# Alimentacion_doble.net
KiCad netlist of a schematic drawn in EAGLE
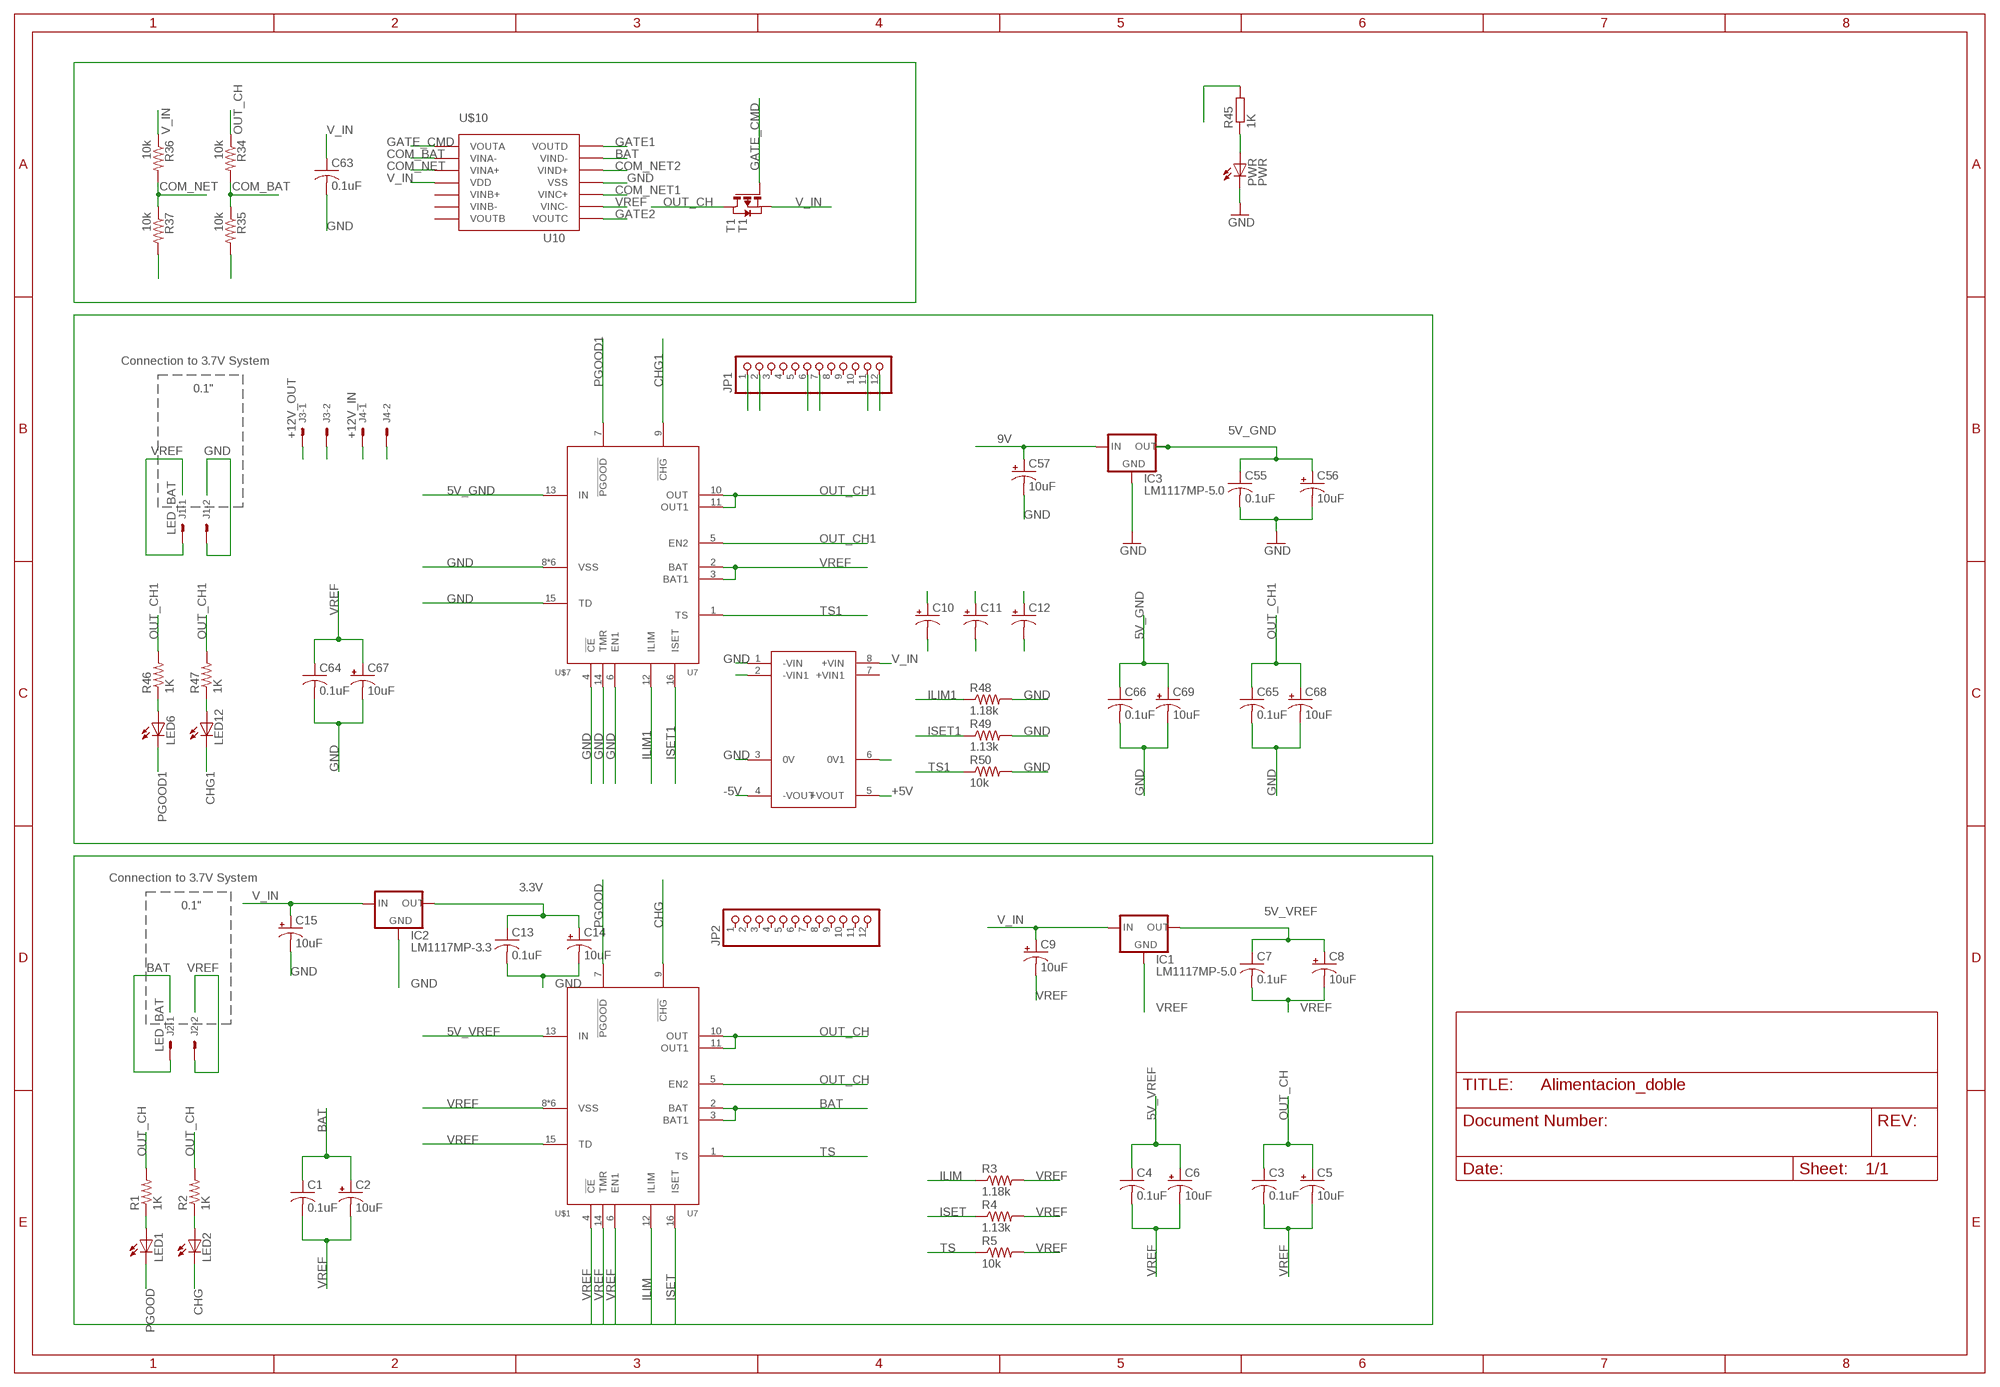
[diagram p0: schematic, sheet 1]

(export (version "E")
  (design (tool "Eeschema 10.0.6"))
  (components
    (comp (ref "C1")
      (value "0.1uF")
      (footprint "eagle-import:C0805K")
      (libsource (lib "eagle-import") (part "C-USC0805K"))
    )
    (comp (ref "C2")
      (value "10uF")
      (footprint "eagle-import:B_3528-21W")
      (libsource (lib "eagle-import") (part "CPOL-USB/3528-21W"))
    )
    (comp (ref "C3")
      (value "0.1uF")
      (footprint "eagle-import:C0805K")
      (libsource (lib "eagle-import") (part "C-USC0805K"))
    )
    (comp (ref "C4")
      (value "0.1uF")
      (footprint "eagle-import:C0805K")
      (libsource (lib "eagle-import") (part "C-USC0805K"))
    )
    (comp (ref "C5")
      (value "10uF")
      (footprint "eagle-import:B_3528-21W")
      (libsource (lib "eagle-import") (part "CPOL-USB/3528-21W"))
    )
    (comp (ref "C6")
      (value "10uF")
      (footprint "eagle-import:B_3528-21W")
      (libsource (lib "eagle-import") (part "CPOL-USB/3528-21W"))
    )
    (comp (ref "C7")
      (value "0.1uF")
      (footprint "eagle-import:C0805K")
      (libsource (lib "eagle-import") (part "C-USC0805K"))
    )
    (comp (ref "C8")
      (value "10uF")
      (footprint "eagle-import:B_3528-21W")
      (libsource (lib "eagle-import") (part "CPOL-USB/3528-21W"))
    )
    (comp (ref "C9")
      (value "10uF")
      (footprint "eagle-import:B_3528-21W")
      (libsource (lib "eagle-import") (part "CPOL-USB/3528-21W"))
    )
    (comp (ref "C10")
      (value "CPOL-USB/3528-21W")
      (footprint "eagle-import:B_3528-21W")
      (libsource (lib "eagle-import") (part "CPOL-USB/3528-21W"))
    )
    (comp (ref "C11")
      (value "CPOL-USB/3528-21W")
      (footprint "eagle-import:B_3528-21W")
      (libsource (lib "eagle-import") (part "CPOL-USB/3528-21W"))
    )
    (comp (ref "C12")
      (value "CPOL-USB/3528-21W")
      (footprint "eagle-import:B_3528-21W")
      (libsource (lib "eagle-import") (part "CPOL-USB/3528-21W"))
    )
    (comp (ref "C13")
      (value "0.1uF")
      (footprint "eagle-import:C0805K")
      (libsource (lib "eagle-import") (part "C-USC0805K"))
    )
    (comp (ref "C14")
      (value "10uF")
      (footprint "eagle-import:B_3528-21W")
      (libsource (lib "eagle-import") (part "CPOL-USB/3528-21W"))
    )
    (comp (ref "C15")
      (value "10uF")
      (footprint "eagle-import:B_3528-21W")
      (libsource (lib "eagle-import") (part "CPOL-USB/3528-21W"))
    )
    (comp (ref "C55")
      (value "0.1uF")
      (footprint "eagle-import:C0805K")
      (libsource (lib "eagle-import") (part "C-USC0805K"))
    )
    (comp (ref "C56")
      (value "10uF")
      (footprint "eagle-import:B_3528-21W")
      (libsource (lib "eagle-import") (part "CPOL-USB/3528-21W"))
    )
    (comp (ref "C57")
      (value "10uF")
      (footprint "eagle-import:B_3528-21W")
      (libsource (lib "eagle-import") (part "CPOL-USB/3528-21W"))
    )
    (comp (ref "C63")
      (value "0.1uF")
      (footprint "eagle-import:C0805K")
      (libsource (lib "eagle-import") (part "C-USC0805K"))
    )
    (comp (ref "C64")
      (value "0.1uF")
      (footprint "eagle-import:C0805K")
      (libsource (lib "eagle-import") (part "C-USC0805K"))
    )
    (comp (ref "C65")
      (value "0.1uF")
      (footprint "eagle-import:C0805K")
      (libsource (lib "eagle-import") (part "C-USC0805K"))
    )
    (comp (ref "C66")
      (value "0.1uF")
      (footprint "eagle-import:C0805K")
      (libsource (lib "eagle-import") (part "C-USC0805K"))
    )
    (comp (ref "C67")
      (value "10uF")
      (footprint "eagle-import:B_3528-21W")
      (libsource (lib "eagle-import") (part "CPOL-USB/3528-21W"))
    )
    (comp (ref "C68")
      (value "10uF")
      (footprint "eagle-import:B_3528-21W")
      (libsource (lib "eagle-import") (part "CPOL-USB/3528-21W"))
    )
    (comp (ref "C69")
      (value "10uF")
      (footprint "eagle-import:B_3528-21W")
      (libsource (lib "eagle-import") (part "CPOL-USB/3528-21W"))
    )
    (comp (ref "IC1")
      (value "LM1117MP-5.0")
      (footprint "eagle-import:SOT223")
      (fields (field (name "MF") "Texas Instruments"))
      (libsource (lib "eagle-import") (part "LM1117?-MP5.0"))
    )
    (comp (ref "IC2")
      (value "LM1117MP-3.3")
      (footprint "eagle-import:SOT223")
      (fields (field (name "MF") "Texas Instruments") (field (name "MPN") "LM1117MP-5.0"))
      (libsource (lib "eagle-import") (part "LM1117?-MP5.0"))
    )
    (comp (ref "IC3")
      (value "LM1117MP-5.0")
      (footprint "eagle-import:SOT223")
      (fields (field (name "MF") "Texas Instruments"))
      (libsource (lib "eagle-import") (part "LM1117?-MP5.0"))
    )
    (comp (ref "J1")
      (value "LED_BAT")
      (footprint "eagle-import:6410-02")
      (libsource (lib "eagle-import") (part "22-?-0227-2021"))
    )
    (comp (ref "J2")
      (value "LED_BAT")
      (footprint "eagle-import:6410-02")
      (libsource (lib "eagle-import") (part "22-?-0227-2021"))
    )
    (comp (ref "J3")
      (value "+12V_OUT")
      (footprint "eagle-import:6410-02")
      (fields (field (name "OC_FARNELL") "unknown") (field (name "OC_NEWARK") "unknown"))
      (libsource (lib "eagle-import") (part "22-?-0227-2021"))
    )
    (comp (ref "J4")
      (value "+12V_IN")
      (footprint "eagle-import:6410-02")
      (fields (field (name "OC_FARNELL") "unknown") (field (name "OC_NEWARK") "unknown"))
      (libsource (lib "eagle-import") (part "22-?-0227-2021"))
    )
    (comp (ref "JP1")
      (value "PINHD-1X12")
      (footprint "eagle-import:1X12")
      (libsource (lib "eagle-import") (part "PINHD-1X12"))
    )
    (comp (ref "JP2")
      (value "PINHD-1X12")
      (footprint "eagle-import:1X12")
      (libsource (lib "eagle-import") (part "PINHD-1X12"))
    )
    (comp (ref "LED1")
      (value "LED3MM")
      (footprint "eagle-import:LED3MM")
      (libsource (lib "eagle-import") (part "LED3MM"))
    )
    (comp (ref "LED2")
      (value "LED3MM")
      (footprint "eagle-import:LED3MM")
      (libsource (lib "eagle-import") (part "LED3MM"))
    )
    (comp (ref "LED6")
      (value "LED3MM")
      (footprint "eagle-import:LED3MM")
      (libsource (lib "eagle-import") (part "LED3MM"))
    )
    (comp (ref "LED12")
      (value "LED3MM")
      (footprint "eagle-import:LED3MM")
      (libsource (lib "eagle-import") (part "LED3MM"))
    )
    (comp (ref "PWR")
      (value "PWR")
      (footprint "eagle-import:LED3MM")
      (libsource (lib "eagle-import") (part "LED3MM"))
    )
    (comp (ref "R1")
      (value "1K")
      (footprint "eagle-import:M0805")
      (libsource (lib "eagle-import") (part "R-US_M0805"))
    )
    (comp (ref "R2")
      (value "1K")
      (footprint "eagle-import:M0805")
      (libsource (lib "eagle-import") (part "R-US_M0805"))
    )
    (comp (ref "R3")
      (value "1.18k")
      (footprint "eagle-import:M0805")
      (libsource (lib "eagle-import") (part "R-US_M0805"))
    )
    (comp (ref "R4")
      (value "1.13k")
      (footprint "eagle-import:M0805")
      (libsource (lib "eagle-import") (part "R-US_M0805"))
    )
    (comp (ref "R5")
      (value "10k")
      (footprint "eagle-import:M0805")
      (libsource (lib "eagle-import") (part "R-US_M0805"))
    )
    (comp (ref "R34")
      (value "10k")
      (footprint "eagle-import:M0805")
      (libsource (lib "eagle-import") (part "R-US_M0805"))
    )
    (comp (ref "R35")
      (value "10k")
      (footprint "eagle-import:M0805")
      (libsource (lib "eagle-import") (part "R-US_M0805"))
    )
    (comp (ref "R36")
      (value "10k")
      (footprint "eagle-import:M0805")
      (libsource (lib "eagle-import") (part "R-US_M0805"))
    )
    (comp (ref "R37")
      (value "10k")
      (footprint "eagle-import:M0805")
      (libsource (lib "eagle-import") (part "R-US_M0805"))
    )
    (comp (ref "R45")
      (value "1K")
      (footprint "eagle-import:R0805")
      (libsource (lib "eagle-import") (part "R-EU_R0805"))
    )
    (comp (ref "R46")
      (value "1K")
      (footprint "eagle-import:M0805")
      (libsource (lib "eagle-import") (part "R-US_M0805"))
    )
    (comp (ref "R47")
      (value "1K")
      (footprint "eagle-import:M0805")
      (libsource (lib "eagle-import") (part "R-US_M0805"))
    )
    (comp (ref "R48")
      (value "1.18k")
      (footprint "eagle-import:M0805")
      (libsource (lib "eagle-import") (part "R-US_M0805"))
    )
    (comp (ref "R49")
      (value "1.13k")
      (footprint "eagle-import:M0805")
      (libsource (lib "eagle-import") (part "R-US_M0805"))
    )
    (comp (ref "R50")
      (value "10k")
      (footprint "eagle-import:M0805")
      (libsource (lib "eagle-import") (part "R-US_M0805"))
    )
    (comp (ref "T1")
      (value "T1")
      (footprint "eagle-import:SOT-23")
      (libsource (lib "eagle-import") (part "PMOSSOT23"))
    )
    (comp (ref "U$1")
      (value "U7")
      (footprint "eagle-import:BQ24232")
      (libsource (lib "eagle-import") (part "BQ24072VQFN-16"))
    )
    (comp (ref "U$2")
      (value "NDTD_CONVERTER")
      (footprint "eagle-import:NDTD_CONVERTER")
      (libsource (lib "eagle-import") (part "NDTD_CONVERTER"))
    )
    (comp (ref "U$7")
      (value "U7")
      (footprint "eagle-import:BQ24232")
      (libsource (lib "eagle-import") (part "BQ24072VQFN-16"))
    )
    (comp (ref "U$10")
      (value "U10")
      (footprint "eagle-import:MCP6294")
      (libsource (lib "eagle-import") (part "MCP6294TSSOP-14"))
    )
  )
  (nets
    (net (code "1") (name "/+5V") (class "Default")
      (node (ref "C12") (pin "+") (pinfunction "+_+") (pintype "passive"))
      (node (ref "JP1") (pin "1") (pinfunction "1_1") (pintype "passive"))
      (node (ref "U$2") (pin "5") (pinfunction "+VOUT_5") (pintype "bidirectional"))
    )
    (net (code "2") (name "/-5V") (class "Default")
      (node (ref "C11") (pin "+") (pinfunction "+_+") (pintype "passive"))
      (node (ref "JP1") (pin "12") (pinfunction "12_12") (pintype "passive"))
      (node (ref "U$2") (pin "4") (pinfunction "-VOUT_4") (pintype "bidirectional"))
    )
    (net (code "3") (name "/3.3V") (class "Default")
      (node (ref "C13") (pin "1") (pinfunction "1_1") (pintype "passive"))
      (node (ref "C14") (pin "+") (pinfunction "+_+") (pintype "passive"))
      (node (ref "IC2") (pin "2") (pinfunction "OUT_2") (pintype "passive"))
      (node (ref "IC2") (pin "4") (pinfunction "OUT_4") (pintype "passive"))
      (node (ref "JP1") (pin "6") (pinfunction "6_6") (pintype "passive"))
    )
    (net (code "4") (name "/5V_GND") (class "Default")
      (node (ref "C55") (pin "1") (pinfunction "1_1") (pintype "passive"))
      (node (ref "C56") (pin "+") (pinfunction "+_+") (pintype "passive"))
      (node (ref "C66") (pin "1") (pinfunction "1_1") (pintype "passive"))
      (node (ref "C69") (pin "+") (pinfunction "+_+") (pintype "passive"))
      (node (ref "IC3") (pin "2") (pinfunction "OUT_2") (pintype "passive"))
      (node (ref "IC3") (pin "4") (pinfunction "OUT_4") (pintype "passive"))
      (node (ref "U$7") (pin "13") (pinfunction "IN_13") (pintype "bidirectional"))
    )
    (net (code "5") (name "/5V_VREF") (class "Default")
      (node (ref "C4") (pin "1") (pinfunction "1_1") (pintype "passive"))
      (node (ref "C6") (pin "+") (pinfunction "+_+") (pintype "passive"))
      (node (ref "C7") (pin "1") (pinfunction "1_1") (pintype "passive"))
      (node (ref "C8") (pin "+") (pinfunction "+_+") (pintype "passive"))
      (node (ref "IC1") (pin "2") (pinfunction "OUT_2") (pintype "passive"))
      (node (ref "IC1") (pin "4") (pinfunction "OUT_4") (pintype "passive"))
      (node (ref "U$1") (pin "13") (pinfunction "IN_13") (pintype "bidirectional"))
    )
    (net (code "6") (name "/9V") (class "Default")
      (node (ref "C57") (pin "+") (pinfunction "+_+") (pintype "passive"))
      (node (ref "IC3") (pin "3") (pinfunction "IN_3") (pintype "input"))
    )
    (net (code "7") (name "/BAT") (class "Default")
      (node (ref "C1") (pin "1") (pinfunction "1_1") (pintype "passive"))
      (node (ref "C2") (pin "+") (pinfunction "+_+") (pintype "passive"))
      (node (ref "J2") (pin "1") (pinfunction "S_1") (pintype "passive"))
      (node (ref "U$1") (pin "2") (pinfunction "BAT_2") (pintype "bidirectional"))
      (node (ref "U$1") (pin "3") (pinfunction "BAT1_3") (pintype "bidirectional"))
      (node (ref "U$10") (pin "VIND-") (pinfunction "VIND-_VIND-") (pintype "bidirectional"))
    )
    (net (code "8") (name "/CHG") (class "Default")
      (node (ref "LED2") (pin "K") (pinfunction "C_K") (pintype "passive"))
      (node (ref "U$1") (pin "9") (pinfunction "~{CHG}_9") (pintype "bidirectional"))
    )
    (net (code "9") (name "/CHG1") (class "Default")
      (node (ref "LED12") (pin "K") (pinfunction "C_K") (pintype "passive"))
      (node (ref "U$7") (pin "9") (pinfunction "~{CHG}_9") (pintype "bidirectional"))
    )
    (net (code "10") (name "/COM_BAT") (class "Default")
      (node (ref "R34") (pin "2") (pinfunction "2_2") (pintype "passive"))
      (node (ref "R35") (pin "1") (pinfunction "1_1") (pintype "passive"))
      (node (ref "U$10") (pin "VINA-") (pinfunction "VINA-_VINA-") (pintype "bidirectional"))
    )
    (net (code "11") (name "/COM_NET") (class "Default")
      (node (ref "R36") (pin "2") (pinfunction "2_2") (pintype "passive"))
      (node (ref "R37") (pin "1") (pinfunction "1_1") (pintype "passive"))
      (node (ref "U$10") (pin "VINA+") (pinfunction "VINA+_VINA+") (pintype "bidirectional"))
    )
    (net (code "12") (name "/COM_NET1") (class "Default")
      (node (ref "U$10") (pin "VINC+") (pinfunction "VINC+_VINC+") (pintype "bidirectional"))
    )
    (net (code "13") (name "/COM_NET2") (class "Default")
      (node (ref "U$10") (pin "VIND+") (pinfunction "VIND+_VIND+") (pintype "bidirectional"))
    )
    (net (code "14") (name "/GATE1") (class "Default")
      (node (ref "U$10") (pin "VOUTD") (pinfunction "VOUTD_VOUTD") (pintype "bidirectional"))
    )
    (net (code "15") (name "/GATE2") (class "Default")
      (node (ref "U$10") (pin "VOUTC") (pinfunction "VOUTC_VOUTC") (pintype "bidirectional"))
    )
    (net (code "16") (name "/GATE_CMD") (class "Default")
      (node (ref "T1") (pin "3") (pinfunction "G_3") (pintype "passive"))
      (node (ref "U$10") (pin "VOUTA") (pinfunction "VOUTA_VOUTA") (pintype "bidirectional"))
    )
    (net (code "17") (name "/ILIM") (class "Default")
      (node (ref "R3") (pin "1") (pinfunction "1_1") (pintype "passive"))
      (node (ref "U$1") (pin "12") (pinfunction "ILIM_12") (pintype "bidirectional"))
    )
    (net (code "18") (name "/ILIM1") (class "Default")
      (node (ref "R48") (pin "1") (pinfunction "1_1") (pintype "passive"))
      (node (ref "U$7") (pin "12") (pinfunction "ILIM_12") (pintype "bidirectional"))
    )
    (net (code "19") (name "/ISET") (class "Default")
      (node (ref "R4") (pin "1") (pinfunction "1_1") (pintype "passive"))
      (node (ref "U$1") (pin "16") (pinfunction "ISET_16") (pintype "bidirectional"))
    )
    (net (code "20") (name "/ISET1") (class "Default")
      (node (ref "R49") (pin "1") (pinfunction "1_1") (pintype "passive"))
      (node (ref "U$7") (pin "16") (pinfunction "ISET_16") (pintype "bidirectional"))
    )
    (net (code "21") (name "/OUT_CH") (class "Default")
      (node (ref "C3") (pin "1") (pinfunction "1_1") (pintype "passive"))
      (node (ref "C5") (pin "+") (pinfunction "+_+") (pintype "passive"))
      (node (ref "R1") (pin "2") (pinfunction "2_2") (pintype "passive"))
      (node (ref "R2") (pin "2") (pinfunction "2_2") (pintype "passive"))
      (node (ref "R34") (pin "1") (pinfunction "1_1") (pintype "passive"))
      (node (ref "T1") (pin "1") (pinfunction "D_1") (pintype "passive"))
      (node (ref "U$1") (pin "10") (pinfunction "OUT_10") (pintype "bidirectional"))
      (node (ref "U$1") (pin "11") (pinfunction "OUT1_11") (pintype "bidirectional"))
      (node (ref "U$1") (pin "5") (pinfunction "EN2_5") (pintype "bidirectional"))
    )
    (net (code "22") (name "/OUT_CH1") (class "Default")
      (node (ref "C65") (pin "1") (pinfunction "1_1") (pintype "passive"))
      (node (ref "C68") (pin "+") (pinfunction "+_+") (pintype "passive"))
      (node (ref "R46") (pin "2") (pinfunction "2_2") (pintype "passive"))
      (node (ref "R47") (pin "2") (pinfunction "2_2") (pintype "passive"))
      (node (ref "U$7") (pin "10") (pinfunction "OUT_10") (pintype "bidirectional"))
      (node (ref "U$7") (pin "11") (pinfunction "OUT1_11") (pintype "bidirectional"))
      (node (ref "U$7") (pin "5") (pinfunction "EN2_5") (pintype "bidirectional"))
    )
    (net (code "23") (name "/PGOOD") (class "Default")
      (node (ref "LED1") (pin "K") (pinfunction "C_K") (pintype "passive"))
      (node (ref "U$1") (pin "7") (pinfunction "~{PGOOD}_7") (pintype "bidirectional"))
    )
    (net (code "24") (name "/PGOOD1") (class "Default")
      (node (ref "LED6") (pin "K") (pinfunction "C_K") (pintype "passive"))
      (node (ref "U$7") (pin "7") (pinfunction "~{PGOOD}_7") (pintype "bidirectional"))
    )
    (net (code "25") (name "/TS") (class "Default")
      (node (ref "R5") (pin "1") (pinfunction "1_1") (pintype "passive"))
      (node (ref "U$1") (pin "1") (pinfunction "TS_1") (pintype "bidirectional"))
    )
    (net (code "26") (name "/TS1") (class "Default")
      (node (ref "R50") (pin "1") (pinfunction "1_1") (pintype "passive"))
      (node (ref "U$7") (pin "1") (pinfunction "TS_1") (pintype "bidirectional"))
    )
    (net (code "27") (name "/VREF") (class "Default")
      (node (ref "C1") (pin "2") (pinfunction "2_2") (pintype "passive"))
      (node (ref "C2") (pin "-") (pinfunction "-_-") (pintype "passive"))
      (node (ref "C3") (pin "2") (pinfunction "2_2") (pintype "passive"))
      (node (ref "C4") (pin "2") (pinfunction "2_2") (pintype "passive"))
      (node (ref "C5") (pin "-") (pinfunction "-_-") (pintype "passive"))
      (node (ref "C6") (pin "-") (pinfunction "-_-") (pintype "passive"))
      (node (ref "C64") (pin "1") (pinfunction "1_1") (pintype "passive"))
      (node (ref "C67") (pin "+") (pinfunction "+_+") (pintype "passive"))
      (node (ref "C7") (pin "2") (pinfunction "2_2") (pintype "passive"))
      (node (ref "C8") (pin "-") (pinfunction "-_-") (pintype "passive"))
      (node (ref "C9") (pin "-") (pinfunction "-_-") (pintype "passive"))
      (node (ref "IC1") (pin "1") (pinfunction "GND_1") (pintype "input"))
      (node (ref "J1") (pin "1") (pinfunction "S_1") (pintype "passive"))
      (node (ref "J2") (pin "2") (pinfunction "S_2") (pintype "passive"))
      (node (ref "R3") (pin "2") (pinfunction "2_2") (pintype "passive"))
      (node (ref "R4") (pin "2") (pinfunction "2_2") (pintype "passive"))
      (node (ref "R5") (pin "2") (pinfunction "2_2") (pintype "passive"))
      (node (ref "U$1") (pin "14") (pinfunction "TMR_14") (pintype "bidirectional"))
      (node (ref "U$1") (pin "15") (pinfunction "TD_15") (pintype "bidirectional"))
      (node (ref "U$1") (pin "4") (pinfunction "~{CE}_4") (pintype "bidirectional"))
      (node (ref "U$1") (pin "6") (pinfunction "EN1_6") (pintype "bidirectional"))
      (node (ref "U$1") (pin "8") (pinfunction "VSS_8") (pintype "bidirectional"))
      (node (ref "U$1") (pin "NA0") (pinfunction "VSS_NA0") (pintype "bidirectional"))
      (node (ref "U$1") (pin "NA1") (pinfunction "VSS_NA1") (pintype "bidirectional"))
      (node (ref "U$1") (pin "NA2") (pinfunction "VSS_NA2") (pintype "bidirectional"))
      (node (ref "U$1") (pin "NA3") (pinfunction "VSS_NA3") (pintype "bidirectional"))
      (node (ref "U$1") (pin "NA4") (pinfunction "VSS_NA4") (pintype "bidirectional"))
      (node (ref "U$10") (pin "VINC-") (pinfunction "VINC-_VINC-") (pintype "bidirectional"))
      (node (ref "U$7") (pin "2") (pinfunction "BAT_2") (pintype "bidirectional"))
      (node (ref "U$7") (pin "3") (pinfunction "BAT1_3") (pintype "bidirectional"))
    )
    (net (code "28") (name "/V_IN") (class "Default")
      (node (ref "C10") (pin "+") (pinfunction "+_+") (pintype "passive"))
      (node (ref "C15") (pin "+") (pinfunction "+_+") (pintype "passive"))
      (node (ref "C63") (pin "1") (pinfunction "1_1") (pintype "passive"))
      (node (ref "C9") (pin "+") (pinfunction "+_+") (pintype "passive"))
      (node (ref "IC1") (pin "3") (pinfunction "IN_3") (pintype "input"))
      (node (ref "IC2") (pin "3") (pinfunction "IN_3") (pintype "input"))
      (node (ref "J3") (pin "1") (pinfunction "S_1") (pintype "passive"))
      (node (ref "J4") (pin "1") (pinfunction "S_1") (pintype "passive"))
      (node (ref "R36") (pin "1") (pinfunction "1_1") (pintype "passive"))
      (node (ref "R45") (pin "2") (pinfunction "2_2") (pintype "passive"))
      (node (ref "T1") (pin "2") (pinfunction "S_2") (pintype "passive"))
      (node (ref "U$10") (pin "VDD") (pinfunction "VDD_VDD") (pintype "bidirectional"))
      (node (ref "U$2") (pin "8") (pinfunction "+VIN_8") (pintype "bidirectional"))
    )
    (net (code "29") (name "GND") (class "Default")
      (node (ref "C10") (pin "-") (pinfunction "-_-") (pintype "passive"))
      (node (ref "C11") (pin "-") (pinfunction "-_-") (pintype "passive"))
      (node (ref "C12") (pin "-") (pinfunction "-_-") (pintype "passive"))
      (node (ref "C13") (pin "2") (pinfunction "2_2") (pintype "passive"))
      (node (ref "C14") (pin "-") (pinfunction "-_-") (pintype "passive"))
      (node (ref "C15") (pin "-") (pinfunction "-_-") (pintype "passive"))
      (node (ref "C55") (pin "2") (pinfunction "2_2") (pintype "passive"))
      (node (ref "C56") (pin "-") (pinfunction "-_-") (pintype "passive"))
      (node (ref "C57") (pin "-") (pinfunction "-_-") (pintype "passive"))
      (node (ref "C63") (pin "2") (pinfunction "2_2") (pintype "passive"))
      (node (ref "C64") (pin "2") (pinfunction "2_2") (pintype "passive"))
      (node (ref "C65") (pin "2") (pinfunction "2_2") (pintype "passive"))
      (node (ref "C66") (pin "2") (pinfunction "2_2") (pintype "passive"))
      (node (ref "C67") (pin "-") (pinfunction "-_-") (pintype "passive"))
      (node (ref "C68") (pin "-") (pinfunction "-_-") (pintype "passive"))
      (node (ref "C69") (pin "-") (pinfunction "-_-") (pintype "passive"))
      (node (ref "IC2") (pin "1") (pinfunction "GND_1") (pintype "input"))
      (node (ref "IC3") (pin "1") (pinfunction "GND_1") (pintype "input"))
      (node (ref "J1") (pin "2") (pinfunction "S_2") (pintype "passive"))
      (node (ref "J3") (pin "2") (pinfunction "S_2") (pintype "passive"))
      (node (ref "J4") (pin "2") (pinfunction "S_2") (pintype "passive"))
      (node (ref "JP1") (pin "11") (pinfunction "11_11") (pintype "passive"))
      (node (ref "JP1") (pin "2") (pinfunction "2_2") (pintype "passive"))
      (node (ref "JP1") (pin "7") (pinfunction "7_7") (pintype "passive"))
      (node (ref "PWR") (pin "K") (pinfunction "C_K") (pintype "passive"))
      (node (ref "R35") (pin "2") (pinfunction "2_2") (pintype "passive"))
      (node (ref "R37") (pin "2") (pinfunction "2_2") (pintype "passive"))
      (node (ref "R48") (pin "2") (pinfunction "2_2") (pintype "passive"))
      (node (ref "R49") (pin "2") (pinfunction "2_2") (pintype "passive"))
      (node (ref "R50") (pin "2") (pinfunction "2_2") (pintype "passive"))
      (node (ref "U$10") (pin "VSS") (pinfunction "VSS_VSS") (pintype "bidirectional"))
      (node (ref "U$2") (pin "1") (pinfunction "-VIN_1") (pintype "bidirectional"))
      (node (ref "U$2") (pin "3") (pinfunction "0V_3") (pintype "bidirectional"))
      (node (ref "U$2") (pin "6") (pinfunction "0V1_6") (pintype "bidirectional"))
      (node (ref "U$7") (pin "14") (pinfunction "TMR_14") (pintype "bidirectional"))
      (node (ref "U$7") (pin "15") (pinfunction "TD_15") (pintype "bidirectional"))
      (node (ref "U$7") (pin "4") (pinfunction "~{CE}_4") (pintype "bidirectional"))
      (node (ref "U$7") (pin "6") (pinfunction "EN1_6") (pintype "bidirectional"))
      (node (ref "U$7") (pin "8") (pinfunction "VSS_8") (pintype "bidirectional"))
      (node (ref "U$7") (pin "NA0") (pinfunction "VSS_NA0") (pintype "bidirectional"))
      (node (ref "U$7") (pin "NA1") (pinfunction "VSS_NA1") (pintype "bidirectional"))
      (node (ref "U$7") (pin "NA2") (pinfunction "VSS_NA2") (pintype "bidirectional"))
      (node (ref "U$7") (pin "NA3") (pinfunction "VSS_NA3") (pintype "bidirectional"))
      (node (ref "U$7") (pin "NA4") (pinfunction "VSS_NA4") (pintype "bidirectional"))
    )
    (net (code "30") (name "Net-(LED1-PadA)") (class "Default")
      (node (ref "LED1") (pin "A") (pinfunction "A_A") (pintype "passive"))
      (node (ref "R1") (pin "1") (pinfunction "1_1") (pintype "passive"))
    )
    (net (code "31") (name "Net-(LED2-PadA)") (class "Default")
      (node (ref "LED2") (pin "A") (pinfunction "A_A") (pintype "passive"))
      (node (ref "R2") (pin "1") (pinfunction "1_1") (pintype "passive"))
    )
    (net (code "32") (name "Net-(LED6-PadA)") (class "Default")
      (node (ref "LED6") (pin "A") (pinfunction "A_A") (pintype "passive"))
      (node (ref "R46") (pin "1") (pinfunction "1_1") (pintype "passive"))
    )
    (net (code "33") (name "Net-(LED12-PadA)") (class "Default")
      (node (ref "LED12") (pin "A") (pinfunction "A_A") (pintype "passive"))
      (node (ref "R47") (pin "1") (pinfunction "1_1") (pintype "passive"))
    )
    (net (code "34") (name "Net-(PWR-PadA)") (class "Default")
      (node (ref "PWR") (pin "A") (pinfunction "A_A") (pintype "passive"))
      (node (ref "R45") (pin "1") (pinfunction "1_1") (pintype "passive"))
    )
    (net (code "35") (name "unconnected-(JP1-Pad3)") (class "Default")
      (node (ref "JP1") (pin "3") (pinfunction "3_3") (pintype "passive"))
    )
    (net (code "36") (name "unconnected-(JP1-Pad4)") (class "Default")
      (node (ref "JP1") (pin "4") (pinfunction "4_4") (pintype "passive"))
    )
    (net (code "37") (name "unconnected-(JP1-Pad5)") (class "Default")
      (node (ref "JP1") (pin "5") (pinfunction "5_5") (pintype "passive"))
    )
    (net (code "38") (name "unconnected-(JP1-Pad8)") (class "Default")
      (node (ref "JP1") (pin "8") (pinfunction "8_8") (pintype "passive"))
    )
    (net (code "39") (name "unconnected-(JP1-Pad9)") (class "Default")
      (node (ref "JP1") (pin "9") (pinfunction "9_9") (pintype "passive"))
    )
    (net (code "40") (name "unconnected-(JP1-Pad10)") (class "Default")
      (node (ref "JP1") (pin "10") (pinfunction "10_10") (pintype "passive"))
    )
    (net (code "41") (name "unconnected-(JP2-Pad1)") (class "Default")
      (node (ref "JP2") (pin "1") (pinfunction "1_1") (pintype "passive"))
    )
    (net (code "42") (name "unconnected-(JP2-Pad2)") (class "Default")
      (node (ref "JP2") (pin "2") (pinfunction "2_2") (pintype "passive"))
    )
    (net (code "43") (name "unconnected-(JP2-Pad3)") (class "Default")
      (node (ref "JP2") (pin "3") (pinfunction "3_3") (pintype "passive"))
    )
    (net (code "44") (name "unconnected-(JP2-Pad4)") (class "Default")
      (node (ref "JP2") (pin "4") (pinfunction "4_4") (pintype "passive"))
    )
    (net (code "45") (name "unconnected-(JP2-Pad5)") (class "Default")
      (node (ref "JP2") (pin "5") (pinfunction "5_5") (pintype "passive"))
    )
    (net (code "46") (name "unconnected-(JP2-Pad6)") (class "Default")
      (node (ref "JP2") (pin "6") (pinfunction "6_6") (pintype "passive"))
    )
    (net (code "47") (name "unconnected-(JP2-Pad7)") (class "Default")
      (node (ref "JP2") (pin "7") (pinfunction "7_7") (pintype "passive"))
    )
    (net (code "48") (name "unconnected-(JP2-Pad8)") (class "Default")
      (node (ref "JP2") (pin "8") (pinfunction "8_8") (pintype "passive"))
    )
    (net (code "49") (name "unconnected-(JP2-Pad9)") (class "Default")
      (node (ref "JP2") (pin "9") (pinfunction "9_9") (pintype "passive"))
    )
    (net (code "50") (name "unconnected-(JP2-Pad10)") (class "Default")
      (node (ref "JP2") (pin "10") (pinfunction "10_10") (pintype "passive"))
    )
    (net (code "51") (name "unconnected-(JP2-Pad11)") (class "Default")
      (node (ref "JP2") (pin "11") (pinfunction "11_11") (pintype "passive"))
    )
    (net (code "52") (name "unconnected-(JP2-Pad12)") (class "Default")
      (node (ref "JP2") (pin "12") (pinfunction "12_12") (pintype "passive"))
    )
    (net (code "53") (name "unconnected-(U$2-+VIN1-Pad7)") (class "Default")
      (node (ref "U$2") (pin "7") (pinfunction "+VIN1_7") (pintype "bidirectional"))
    )
    (net (code "54") (name "unconnected-(U$2--VIN1-Pad2)") (class "Default")
      (node (ref "U$2") (pin "2") (pinfunction "-VIN1_2") (pintype "bidirectional"))
    )
    (net (code "55") (name "unconnected-(U$10-PadVINB+)") (class "Default")
      (node (ref "U$10") (pin "VINB+") (pinfunction "VINB+_VINB+") (pintype "bidirectional"))
    )
    (net (code "56") (name "unconnected-(U$10-PadVINB-)") (class "Default")
      (node (ref "U$10") (pin "VINB-") (pinfunction "VINB-_VINB-") (pintype "bidirectional"))
    )
    (net (code "57") (name "unconnected-(U$10-PadVOUTB)") (class "Default")
      (node (ref "U$10") (pin "VOUTB") (pinfunction "VOUTB_VOUTB") (pintype "bidirectional"))
    )
  )
)
